# bsides2017.net
KiCad netlist of a schematic drawn in EAGLE
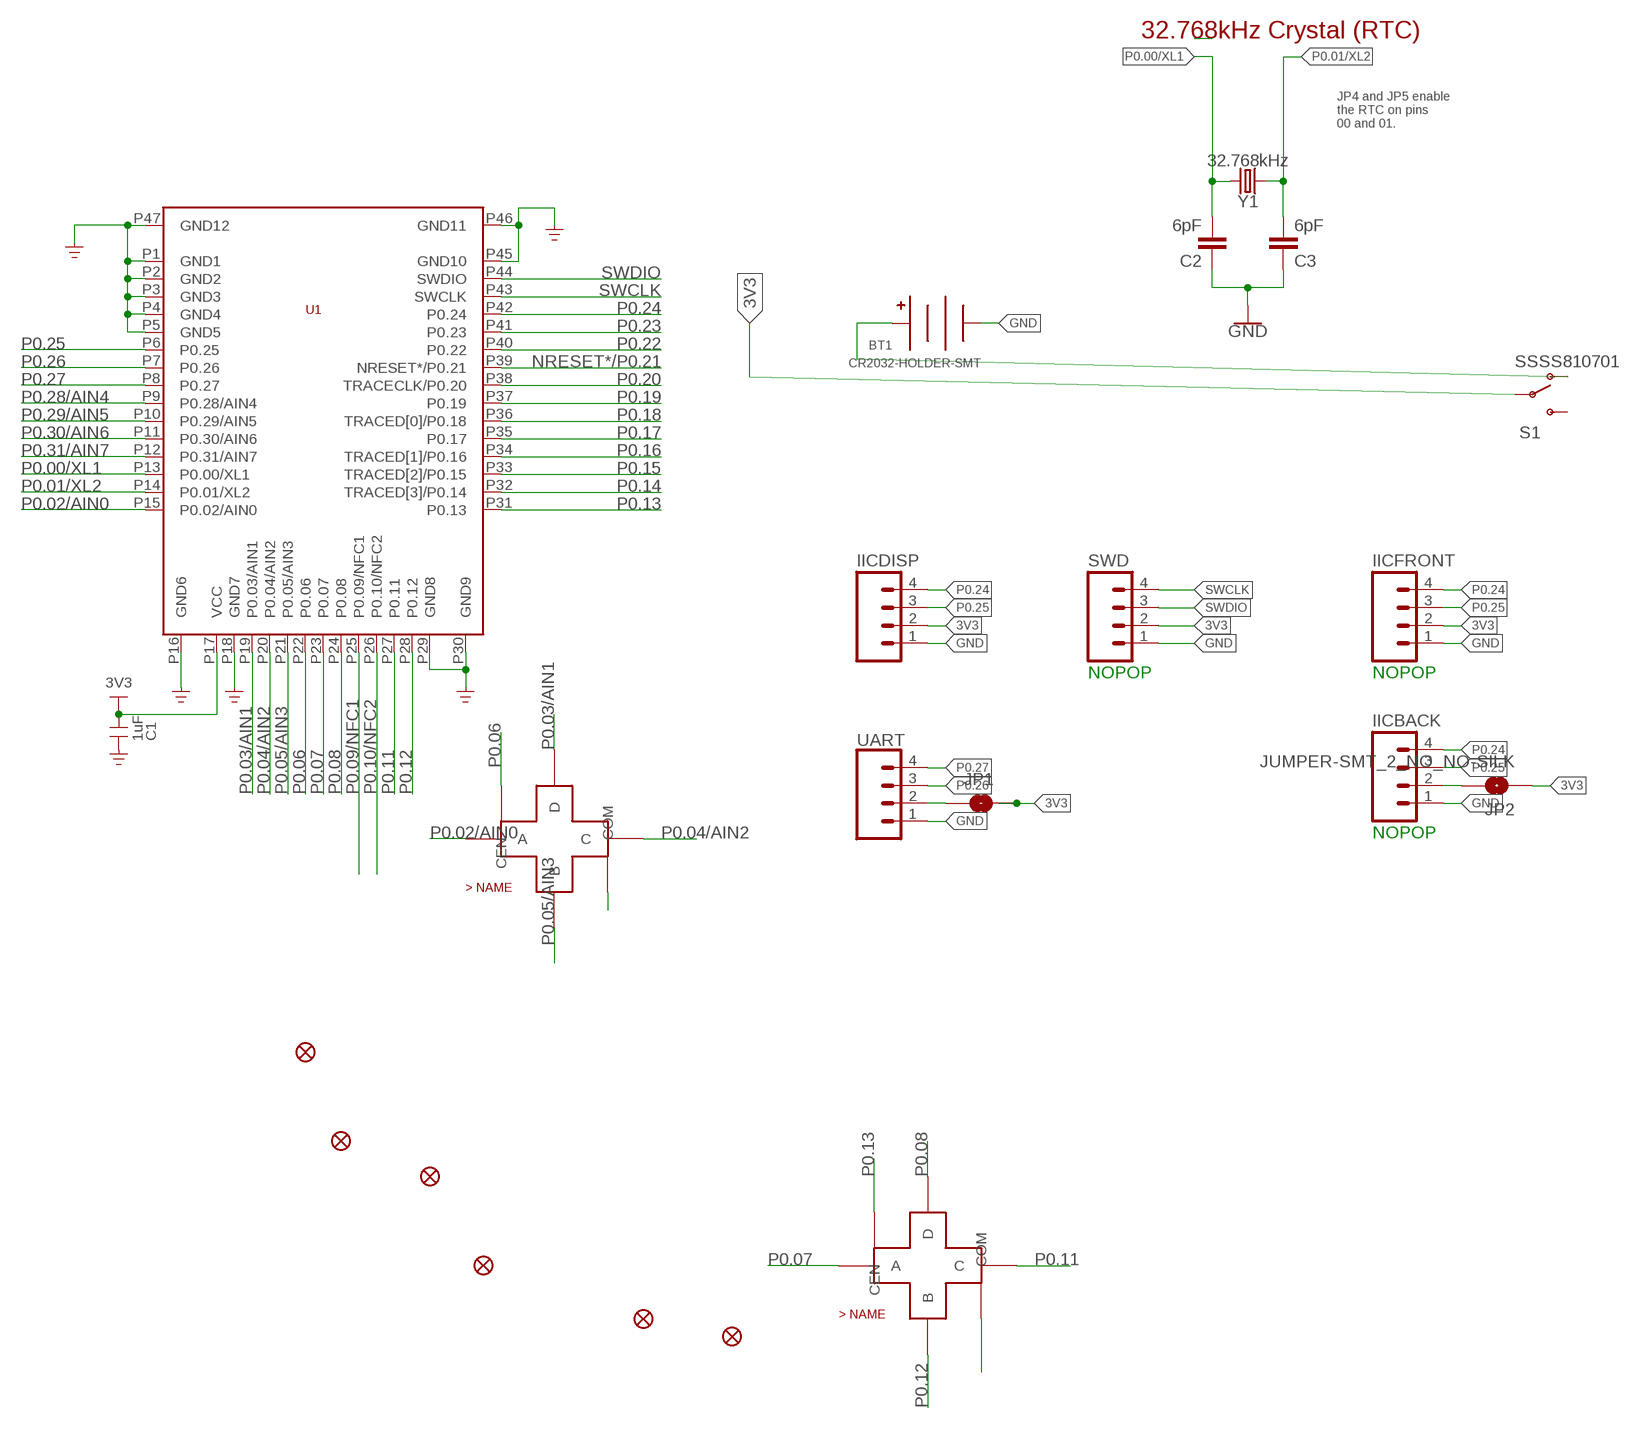
[diagram p0: schematic, sheet 1]

(export (version "E")
  (design (tool "Eeschema 10.0.6"))
  (components
    (comp (ref "BT1")
      (value "CR2032-HOLDER-SMT")
      (footprint "eagle-import:S8211-46R")
      (libsource (lib "eagle-import") (part "CR2032-HOLDER-SMT"))
    )
    (comp (ref "C1")
      (value "1uF")
      (footprint "eagle-import:SMD0603")
      (description "CAP CER 1UF 6.3V 10% X5R 0603")
      (fields (field (name "MFR") "Samsung"))
      (libsource (lib "eagle-import") (part "C-0603"))
    )
    (comp (ref "C2")
      (value "6pF")
      (footprint "eagle-import:0402")
      (libsource (lib "eagle-import") (part "15PF-0402-50V-5%"))
    )
    (comp (ref "C3")
      (value "6pF")
      (footprint "eagle-import:0402")
      (libsource (lib "eagle-import") (part "15PF-0402-50V-5%"))
    )
    (comp (ref "FID1")
      (value "FIDUCIAL1X2")
      (footprint "eagle-import:FIDUCIAL-1X2")
      (libsource (lib "eagle-import") (part "FIDUCIAL1X2"))
    )
    (comp (ref "FID2")
      (value "FIDUCIAL1X2")
      (footprint "eagle-import:FIDUCIAL-1X2")
      (libsource (lib "eagle-import") (part "FIDUCIAL1X2"))
    )
    (comp (ref "FID3")
      (value "FIDUCIAL1X2")
      (footprint "eagle-import:FIDUCIAL-1X2")
      (libsource (lib "eagle-import") (part "FIDUCIAL1X2"))
    )
    (comp (ref "FID4")
      (value "FIDUCIAL1X2")
      (footprint "eagle-import:FIDUCIAL-1X2")
      (libsource (lib "eagle-import") (part "FIDUCIAL1X2"))
    )
    (comp (ref "FID5")
      (value "FIDUCIAL1X2")
      (footprint "eagle-import:FIDUCIAL-1X2")
      (libsource (lib "eagle-import") (part "FIDUCIAL1X2"))
    )
    (comp (ref "FID6")
      (value "FIDUCIAL1X2")
      (footprint "eagle-import:FIDUCIAL-1X2")
      (libsource (lib "eagle-import") (part "FIDUCIAL1X2"))
    )
    (comp (ref "IICBACK")
      (value "M04LOCK")
      (footprint "eagle-import:1X04_LOCK@1")
      (libsource (lib "eagle-import") (part "M04LOCK"))
    )
    (comp (ref "IICDISP")
      (value "M04LOCK")
      (footprint "eagle-import:1X04_LOCK@1")
      (libsource (lib "eagle-import") (part "M04LOCK"))
    )
    (comp (ref "IICFRONT")
      (value "M04LOCK")
      (footprint "eagle-import:1X04_LOCK@1")
      (libsource (lib "eagle-import") (part "M04LOCK"))
    )
    (comp (ref "JP1")
      (value "JUMPER-SMT_2_NO_NO-SILK")
      (footprint "eagle-import:SMT-JUMPER_2_NO_NO-SILK")
      (libsource (lib "eagle-import") (part "JUMPER-SMT_2_NO_NO-SILK"))
    )
    (comp (ref "JP2")
      (value "JUMPER-SMT_2_NO_NO-SILK")
      (footprint "eagle-import:SMT-JUMPER_2_NO_NO-SILK")
      (libsource (lib "eagle-import") (part "JUMPER-SMT_2_NO_NO-SILK"))
    )
    (comp (ref "S1")
      (value "SSSS810701")
      (footprint "eagle-import:SSSS8")
      (libsource (lib "eagle-import") (part "SSSS810701"))
    )
    (comp (ref "SWD")
      (value "M04LOCK")
      (footprint "eagle-import:1X04_LOCK@1")
      (libsource (lib "eagle-import") (part "M04LOCK"))
    )
    (comp (ref "U$6")
      (value "SKRHABE010")
      (footprint "eagle-import:SKRHABE010")
      (libsource (lib "eagle-import") (part "SKRHABE010"))
    )
    (comp (ref "U$7")
      (value "SKRHABE010")
      (footprint "eagle-import:SKRHABE010")
      (libsource (lib "eagle-import") (part "SKRHABE010"))
    )
    (comp (ref "U1")
      (value "BMD-300")
      (footprint "eagle-import:BMD-300")
      (libsource (lib "eagle-import") (part "BMD-300"))
    )
    (comp (ref "UART")
      (value "CONN_04SMD")
      (footprint "eagle-import:1X04_SMD_RA_MALE")
      (libsource (lib "eagle-import") (part "CONN_04SMD"))
    )
    (comp (ref "Y1")
      (value "32.768kHz")
      (footprint "eagle-import:CRYSTAL-SMD-3.2X1.5MM")
      (libsource (lib "eagle-import") (part "CRYSTAL-32.768KHZSMD-3.2X1.5"))
    )
  )
  (nets
    (net (code "1") (name "/NRESET*{slash}P0.21") (class "Default")
      (node (ref "U1") (pin "P39") (pinfunction "NRESET*/P0.21_P39") (pintype "bidirectional"))
    )
    (net (code "2") (name "/P0.02{slash}AIN0") (class "Default")
      (node (ref "U$6") (pin "P$1") (pinfunction "A_P$1") (pintype "bidirectional"))
      (node (ref "U1") (pin "P15") (pinfunction "P0.02/AIN0_P15") (pintype "bidirectional"))
    )
    (net (code "3") (name "/P0.03{slash}AIN1") (class "Default")
      (node (ref "U$6") (pin "P$6") (pinfunction "D_P$6") (pintype "bidirectional"))
      (node (ref "U1") (pin "P19") (pinfunction "P0.03/AIN1_P19") (pintype "bidirectional"))
    )
    (net (code "4") (name "/P0.04{slash}AIN2") (class "Default")
      (node (ref "U$6") (pin "P$3") (pinfunction "C_P$3") (pintype "bidirectional"))
      (node (ref "U1") (pin "P20") (pinfunction "P0.04/AIN2_P20") (pintype "bidirectional"))
    )
    (net (code "5") (name "/P0.05{slash}AIN3") (class "Default")
      (node (ref "U$6") (pin "P$4") (pinfunction "B_P$4") (pintype "bidirectional"))
      (node (ref "U1") (pin "P21") (pinfunction "P0.05/AIN3_P21") (pintype "bidirectional"))
    )
    (net (code "6") (name "/P0.06") (class "Default")
      (node (ref "U$6") (pin "P$2") (pinfunction "CEN_P$2") (pintype "bidirectional"))
      (node (ref "U1") (pin "P22") (pinfunction "P0.06_P22") (pintype "bidirectional"))
    )
    (net (code "7") (name "/P0.07") (class "Default")
      (node (ref "U$7") (pin "P$1") (pinfunction "A_P$1") (pintype "bidirectional"))
      (node (ref "U1") (pin "P23") (pinfunction "P0.07_P23") (pintype "bidirectional"))
    )
    (net (code "8") (name "/P0.08") (class "Default")
      (node (ref "U$7") (pin "P$6") (pinfunction "D_P$6") (pintype "bidirectional"))
      (node (ref "U1") (pin "P24") (pinfunction "P0.08_P24") (pintype "bidirectional"))
    )
    (net (code "9") (name "/P0.09{slash}NFC1") (class "Default")
      (node (ref "U1") (pin "P25") (pinfunction "P0.09/NFC1_P25") (pintype "bidirectional"))
    )
    (net (code "10") (name "/P0.10{slash}NFC2") (class "Default")
      (node (ref "U1") (pin "P26") (pinfunction "P0.10/NFC2_P26") (pintype "bidirectional"))
    )
    (net (code "11") (name "/P0.11") (class "Default")
      (node (ref "U$7") (pin "P$3") (pinfunction "C_P$3") (pintype "bidirectional"))
      (node (ref "U1") (pin "P27") (pinfunction "P0.11_P27") (pintype "bidirectional"))
    )
    (net (code "12") (name "/P0.12") (class "Default")
      (node (ref "U$7") (pin "P$4") (pinfunction "B_P$4") (pintype "bidirectional"))
      (node (ref "U1") (pin "P28") (pinfunction "P0.12_P28") (pintype "bidirectional"))
    )
    (net (code "13") (name "/P0.13") (class "Default")
      (node (ref "U$7") (pin "P$2") (pinfunction "CEN_P$2") (pintype "bidirectional"))
      (node (ref "U1") (pin "P31") (pinfunction "P0.13_P31") (pintype "bidirectional"))
    )
    (net (code "14") (name "/P0.14") (class "Default")
      (node (ref "U1") (pin "P32") (pinfunction "TRACED[3]/P0.14_P32") (pintype "bidirectional"))
    )
    (net (code "15") (name "/P0.15") (class "Default")
      (node (ref "U1") (pin "P33") (pinfunction "TRACED[2]/P0.15_P33") (pintype "bidirectional"))
    )
    (net (code "16") (name "/P0.16") (class "Default")
      (node (ref "U1") (pin "P34") (pinfunction "TRACED[1]/P0.16_P34") (pintype "bidirectional"))
    )
    (net (code "17") (name "/P0.17") (class "Default")
      (node (ref "U1") (pin "P35") (pinfunction "P0.17_P35") (pintype "bidirectional"))
    )
    (net (code "18") (name "/P0.18") (class "Default")
      (node (ref "U1") (pin "P36") (pinfunction "TRACED[0]/P0.18_P36") (pintype "bidirectional"))
    )
    (net (code "19") (name "/P0.19") (class "Default")
      (node (ref "U1") (pin "P37") (pinfunction "P0.19_P37") (pintype "bidirectional"))
    )
    (net (code "20") (name "/P0.20") (class "Default")
      (node (ref "U1") (pin "P38") (pinfunction "TRACECLK/P0.20_P38") (pintype "bidirectional"))
    )
    (net (code "21") (name "/P0.22") (class "Default")
      (node (ref "U1") (pin "P40") (pinfunction "P0.22_P40") (pintype "bidirectional"))
    )
    (net (code "22") (name "/P0.23") (class "Default")
      (node (ref "U1") (pin "P41") (pinfunction "P0.23_P41") (pintype "bidirectional"))
    )
    (net (code "23") (name "/P0.28{slash}AIN4") (class "Default")
      (node (ref "U1") (pin "P9") (pinfunction "P0.28/AIN4_P9") (pintype "bidirectional"))
    )
    (net (code "24") (name "/P0.29{slash}AIN5") (class "Default")
      (node (ref "U1") (pin "P10") (pinfunction "P0.29/AIN5_P10") (pintype "bidirectional"))
    )
    (net (code "25") (name "/P0.30{slash}AIN6") (class "Default")
      (node (ref "U1") (pin "P11") (pinfunction "P0.30/AIN6_P11") (pintype "bidirectional"))
    )
    (net (code "26") (name "/P0.31{slash}AIN7") (class "Default")
      (node (ref "U1") (pin "P12") (pinfunction "P0.31/AIN7_P12") (pintype "bidirectional"))
    )
    (net (code "27") (name "3V3") (class "Default")
      (node (ref "C1") (pin "2") (pinfunction "3_2") (pintype "passive"))
      (node (ref "IICDISP") (pin "2") (pinfunction "2_2") (pintype "passive"))
      (node (ref "IICFRONT") (pin "2") (pinfunction "2_2") (pintype "passive"))
      (node (ref "JP1") (pin "2") (pinfunction "2_2") (pintype "passive"))
      (node (ref "JP2") (pin "1") (pinfunction "1_1") (pintype "passive"))
      (node (ref "S1") (pin "P$2") (pinfunction "P_P$2") (pintype "passive"))
      (node (ref "SWD") (pin "2") (pinfunction "2_2") (pintype "passive"))
      (node (ref "U1") (pin "P17") (pinfunction "VCC_P17") (pintype "bidirectional"))
    )
    (net (code "28") (name "GND") (class "Default")
      (node (ref "BT1") (pin "NEG") (pinfunction "NEG_NEG") (pintype "bidirectional"))
      (node (ref "C1") (pin "1") (pinfunction "1_1") (pintype "passive"))
      (node (ref "C2") (pin "1") (pinfunction "1_1") (pintype "passive"))
      (node (ref "C3") (pin "1") (pinfunction "1_1") (pintype "passive"))
      (node (ref "IICBACK") (pin "1") (pinfunction "1_1") (pintype "passive"))
      (node (ref "IICDISP") (pin "1") (pinfunction "1_1") (pintype "passive"))
      (node (ref "IICFRONT") (pin "1") (pinfunction "1_1") (pintype "passive"))
      (node (ref "SWD") (pin "1") (pinfunction "1_1") (pintype "passive"))
      (node (ref "U$6") (pin "P$5") (pinfunction "COM_P$5") (pintype "power_in"))
      (node (ref "U$6") (pin "P$7") (pinfunction "COM_P$7") (pintype "power_in"))
      (node (ref "U$6") (pin "P$8") (pinfunction "COM_P$8") (pintype "power_in"))
      (node (ref "U$7") (pin "P$5") (pinfunction "COM_P$5") (pintype "power_in"))
      (node (ref "U$7") (pin "P$7") (pinfunction "COM_P$7") (pintype "power_in"))
      (node (ref "U$7") (pin "P$8") (pinfunction "COM_P$8") (pintype "power_in"))
      (node (ref "U1") (pin "P1") (pinfunction "GND1_P1") (pintype "bidirectional"))
      (node (ref "U1") (pin "P16") (pinfunction "GND6_P16") (pintype "bidirectional"))
      (node (ref "U1") (pin "P18") (pinfunction "GND7_P18") (pintype "bidirectional"))
      (node (ref "U1") (pin "P2") (pinfunction "GND2_P2") (pintype "bidirectional"))
      (node (ref "U1") (pin "P29") (pinfunction "GND8_P29") (pintype "bidirectional"))
      (node (ref "U1") (pin "P3") (pinfunction "GND3_P3") (pintype "bidirectional"))
      (node (ref "U1") (pin "P30") (pinfunction "GND9_P30") (pintype "bidirectional"))
      (node (ref "U1") (pin "P4") (pinfunction "GND4_P4") (pintype "bidirectional"))
      (node (ref "U1") (pin "P45") (pinfunction "GND10_P45") (pintype "bidirectional"))
      (node (ref "U1") (pin "P46") (pinfunction "GND11_P46") (pintype "bidirectional"))
      (node (ref "U1") (pin "P47") (pinfunction "GND12_P47") (pintype "bidirectional"))
      (node (ref "U1") (pin "P5") (pinfunction "GND5_P5") (pintype "bidirectional"))
      (node (ref "UART") (pin "1") (pinfunction "1_1") (pintype "passive"))
    )
    (net (code "29") (name "Net-(IICBACK-Pad2)") (class "Default")
      (node (ref "IICBACK") (pin "2") (pinfunction "2_2") (pintype "passive"))
      (node (ref "JP2") (pin "2") (pinfunction "2_2") (pintype "passive"))
    )
    (net (code "30") (name "Net-(JP1-Pad1)") (class "Default")
      (node (ref "JP1") (pin "1") (pinfunction "1_1") (pintype "passive"))
      (node (ref "UART") (pin "2") (pinfunction "2_2") (pintype "passive"))
    )
    (net (code "31") (name "Net-(S1-O)") (class "Default")
      (node (ref "BT1") (pin "POS0") (pinfunction "POS_POS0") (pintype "bidirectional"))
      (node (ref "BT1") (pin "POS1") (pinfunction "POS_POS1") (pintype "bidirectional"))
      (node (ref "S1") (pin "P$3") (pinfunction "O_P$3") (pintype "passive"))
    )
    (net (code "32") (name "P0.00{slash}XL1") (class "Default")
      (node (ref "C2") (pin "2") (pinfunction "2_2") (pintype "passive"))
      (node (ref "U1") (pin "P13") (pinfunction "P0.00/XL1_P13") (pintype "bidirectional"))
      (node (ref "Y1") (pin "P$2") (pinfunction "2_P$2") (pintype "passive"))
    )
    (net (code "33") (name "P0.01{slash}XL2") (class "Default")
      (node (ref "C3") (pin "2") (pinfunction "2_2") (pintype "passive"))
      (node (ref "U1") (pin "P14") (pinfunction "P0.01/XL2_P14") (pintype "bidirectional"))
      (node (ref "Y1") (pin "P$1") (pinfunction "1_P$1") (pintype "passive"))
    )
    (net (code "34") (name "P0.24") (class "Default")
      (node (ref "IICBACK") (pin "4") (pinfunction "4_4") (pintype "passive"))
      (node (ref "IICDISP") (pin "4") (pinfunction "4_4") (pintype "passive"))
      (node (ref "IICFRONT") (pin "4") (pinfunction "4_4") (pintype "passive"))
      (node (ref "U1") (pin "P42") (pinfunction "P0.24_P42") (pintype "bidirectional"))
    )
    (net (code "35") (name "P0.25") (class "Default")
      (node (ref "IICBACK") (pin "3") (pinfunction "3_3") (pintype "passive"))
      (node (ref "IICDISP") (pin "3") (pinfunction "3_3") (pintype "passive"))
      (node (ref "IICFRONT") (pin "3") (pinfunction "3_3") (pintype "passive"))
      (node (ref "U1") (pin "P6") (pinfunction "P0.25_P6") (pintype "bidirectional"))
    )
    (net (code "36") (name "P0.26") (class "Default")
      (node (ref "U1") (pin "P7") (pinfunction "P0.26_P7") (pintype "bidirectional"))
      (node (ref "UART") (pin "3") (pinfunction "3_3") (pintype "passive"))
    )
    (net (code "37") (name "P0.27") (class "Default")
      (node (ref "U1") (pin "P8") (pinfunction "P0.27_P8") (pintype "bidirectional"))
      (node (ref "UART") (pin "4") (pinfunction "4_4") (pintype "passive"))
    )
    (net (code "38") (name "SWCLK") (class "Default")
      (node (ref "SWD") (pin "4") (pinfunction "4_4") (pintype "passive"))
      (node (ref "U1") (pin "P43") (pinfunction "SWCLK_P43") (pintype "bidirectional"))
    )
    (net (code "39") (name "SWDIO") (class "Default")
      (node (ref "SWD") (pin "3") (pinfunction "3_3") (pintype "passive"))
      (node (ref "U1") (pin "P44") (pinfunction "SWDIO_P44") (pintype "bidirectional"))
    )
    (net (code "40") (name "unconnected-(S1-S-PadP$1)") (class "Default")
      (node (ref "S1") (pin "P$1") (pinfunction "S_P$1") (pintype "passive"))
    )
  )
)
